# decoder.net
KiCad netlist of a schematic drawn in EAGLE
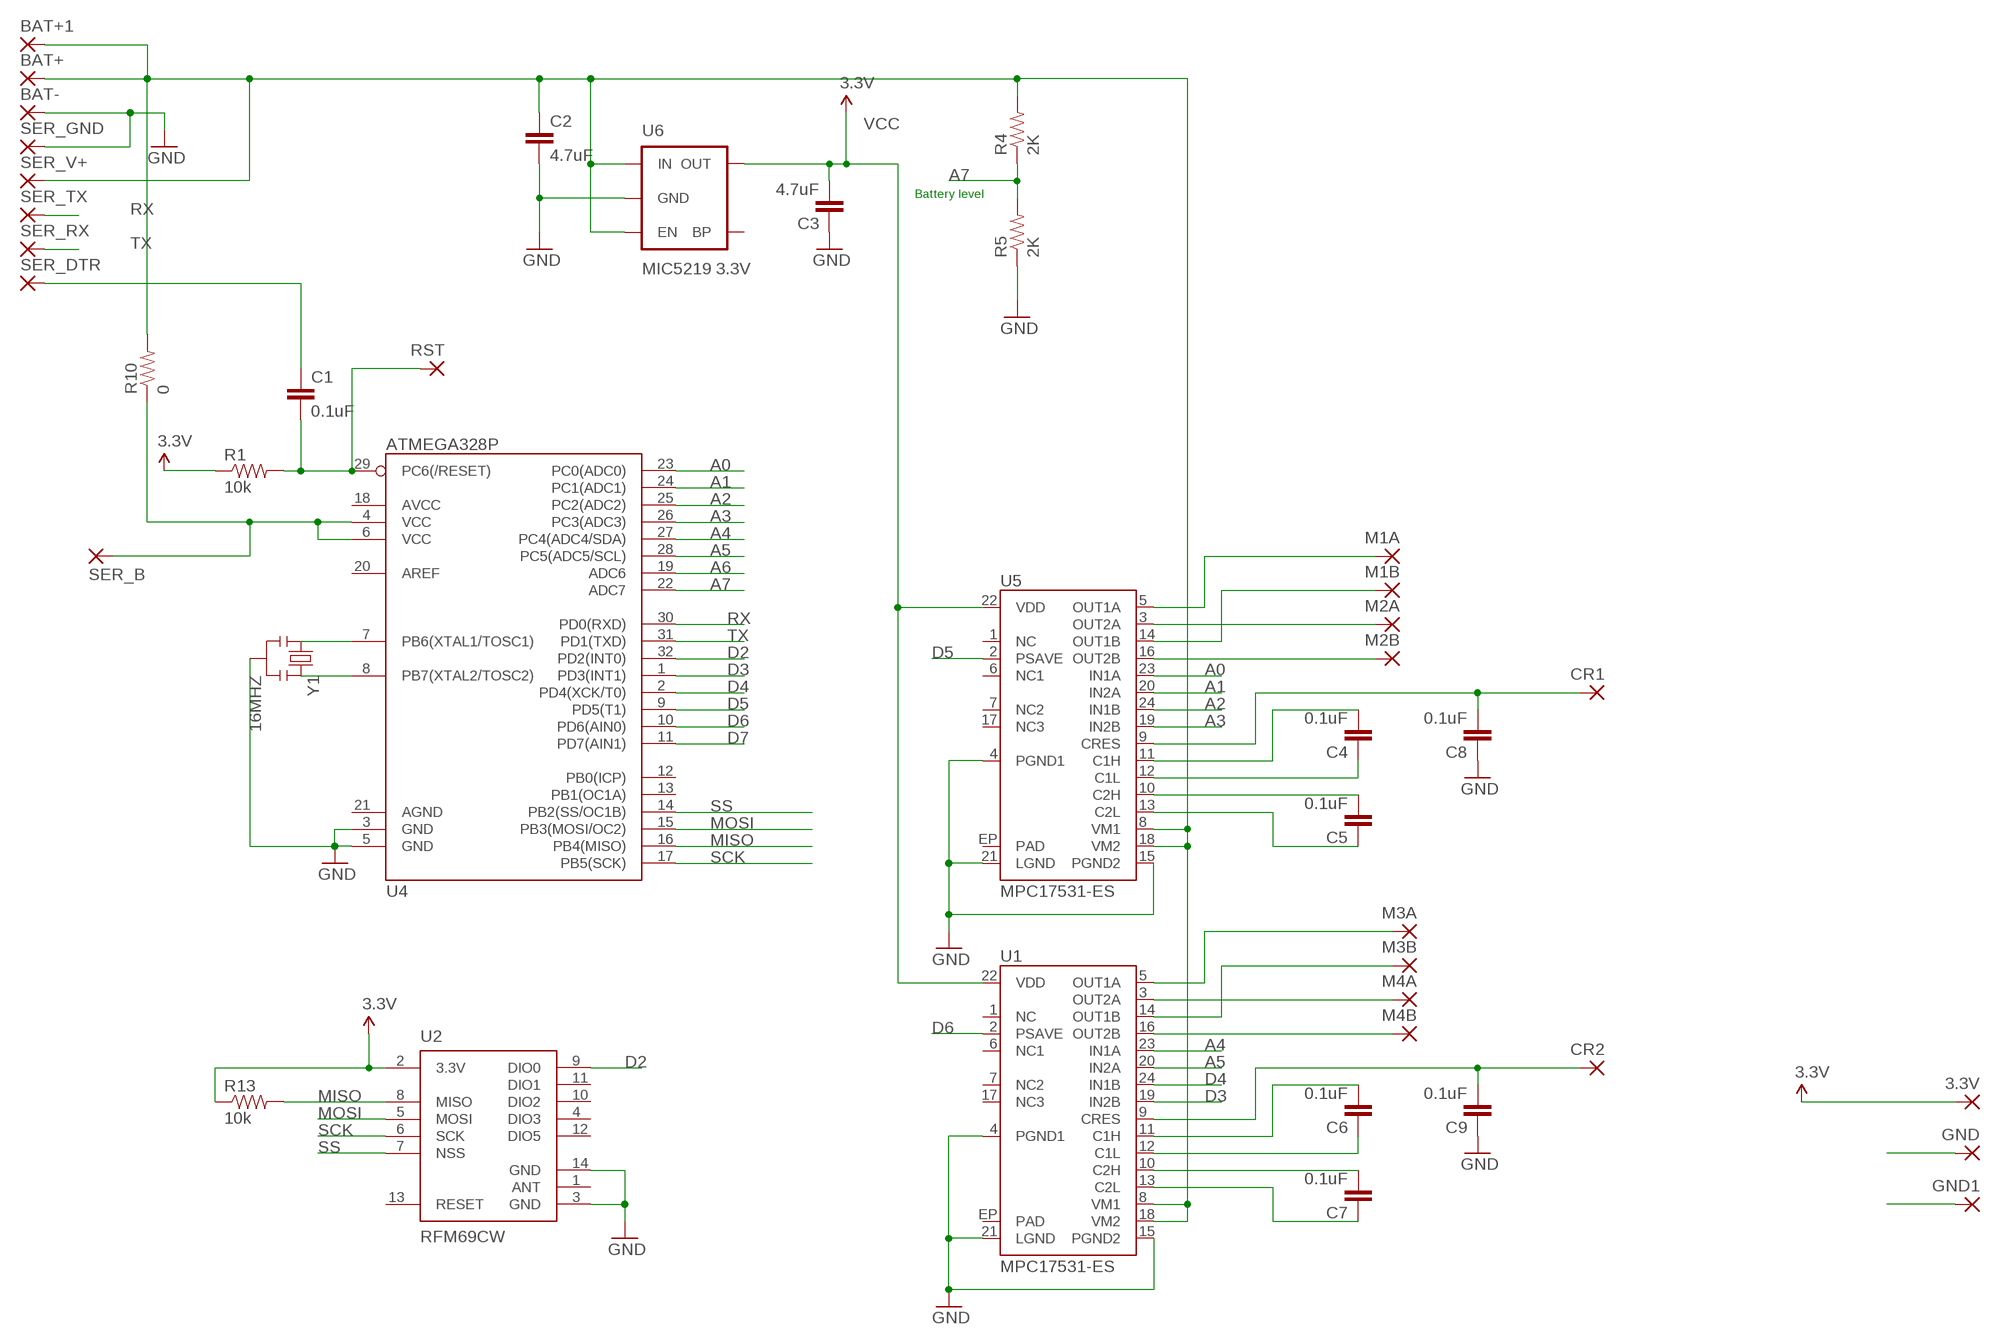
[diagram p0: schematic, sheet 1]

(export (version "E")
  (design (tool "Eeschema 10.0.6"))
  (components
    (comp (ref "3.3V")
      (value "SMD2")
      (footprint "eagle-import:SMD1,27-2,54")
      (libsource (lib "eagle-import") (part "SMD2"))
    )
    (comp (ref "BAT+")
      (value "SMD2")
      (footprint "eagle-import:SMD1,27-2,54")
      (libsource (lib "eagle-import") (part "SMD2"))
    )
    (comp (ref "BAT+1")
      (value "SMD2")
      (footprint "eagle-import:SMD1,27-2,54")
      (libsource (lib "eagle-import") (part "SMD2"))
    )
    (comp (ref "BAT-")
      (value "SMD2")
      (footprint "eagle-import:SMD1,27-2,54")
      (libsource (lib "eagle-import") (part "SMD2"))
    )
    (comp (ref "C1")
      (value "0.1uF")
      (footprint "eagle-import:0805")
      (libsource (lib "eagle-import") (part "CAP0805"))
    )
    (comp (ref "C2")
      (value "4.7uF")
      (footprint "eagle-import:0805")
      (libsource (lib "eagle-import") (part "CAP0805"))
    )
    (comp (ref "C3")
      (value "4.7uF")
      (footprint "eagle-import:0805")
      (libsource (lib "eagle-import") (part "CAP0805"))
    )
    (comp (ref "C4")
      (value "0.1uF")
      (footprint "eagle-import:0805")
      (libsource (lib "eagle-import") (part "CAP0805"))
    )
    (comp (ref "C5")
      (value "0.1uF")
      (footprint "eagle-import:0805")
      (libsource (lib "eagle-import") (part "CAP0805"))
    )
    (comp (ref "C6")
      (value "0.1uF")
      (footprint "eagle-import:0805")
      (libsource (lib "eagle-import") (part "CAP0805"))
    )
    (comp (ref "C7")
      (value "0.1uF")
      (footprint "eagle-import:0805")
      (libsource (lib "eagle-import") (part "CAP0805"))
    )
    (comp (ref "C8")
      (value "0.1uF")
      (footprint "eagle-import:0805")
      (libsource (lib "eagle-import") (part "CAP0805"))
    )
    (comp (ref "C9")
      (value "0.1uF")
      (footprint "eagle-import:0805")
      (libsource (lib "eagle-import") (part "CAP0805"))
    )
    (comp (ref "CR1")
      (value "SMD2")
      (footprint "eagle-import:SMD1,27-2,54")
      (libsource (lib "eagle-import") (part "SMD2"))
    )
    (comp (ref "CR2")
      (value "SMD2")
      (footprint "eagle-import:SMD1,27-2,54")
      (libsource (lib "eagle-import") (part "SMD2"))
    )
    (comp (ref "GND")
      (value "SMD2")
      (footprint "eagle-import:SMD1,27-2,54")
      (libsource (lib "eagle-import") (part "SMD2"))
    )
    (comp (ref "GND1")
      (value "SMD2")
      (footprint "eagle-import:SMD1,27-2,54")
      (libsource (lib "eagle-import") (part "SMD2"))
    )
    (comp (ref "M1A")
      (value "SMD2")
      (footprint "eagle-import:SMD1,27-2,54")
      (libsource (lib "eagle-import") (part "SMD2"))
    )
    (comp (ref "M1B")
      (value "SMD2")
      (footprint "eagle-import:SMD1,27-2,54")
      (libsource (lib "eagle-import") (part "SMD2"))
    )
    (comp (ref "M2A")
      (value "SMD2")
      (footprint "eagle-import:SMD1,27-2,54")
      (libsource (lib "eagle-import") (part "SMD2"))
    )
    (comp (ref "M2B")
      (value "SMD2")
      (footprint "eagle-import:SMD1,27-2,54")
      (libsource (lib "eagle-import") (part "SMD2"))
    )
    (comp (ref "M3A")
      (value "SMD2")
      (footprint "eagle-import:SMD1,27-2,54")
      (libsource (lib "eagle-import") (part "SMD2"))
    )
    (comp (ref "M3B")
      (value "SMD2")
      (footprint "eagle-import:SMD1,27-2,54")
      (libsource (lib "eagle-import") (part "SMD2"))
    )
    (comp (ref "M4A")
      (value "SMD2")
      (footprint "eagle-import:SMD1,27-2,54")
      (libsource (lib "eagle-import") (part "SMD2"))
    )
    (comp (ref "M4B")
      (value "SMD2")
      (footprint "eagle-import:SMD1,27-2,54")
      (libsource (lib "eagle-import") (part "SMD2"))
    )
    (comp (ref "R1")
      (value "10k")
      (footprint "eagle-import:0603-RES")
      (libsource (lib "eagle-import") (part "RESISTOR0603-RES"))
    )
    (comp (ref "R4")
      (value "2K")
      (footprint "eagle-import:0603-RES")
      (libsource (lib "eagle-import") (part "RESISTOR0603-RES"))
    )
    (comp (ref "R5")
      (value "2K")
      (footprint "eagle-import:0603-RES")
      (libsource (lib "eagle-import") (part "RESISTOR0603-RES"))
    )
    (comp (ref "R10")
      (value "0")
      (footprint "eagle-import:0603-RES")
      (libsource (lib "eagle-import") (part "RESISTOR0603-RES"))
    )
    (comp (ref "R13")
      (value "10k")
      (footprint "eagle-import:0603-RES")
      (libsource (lib "eagle-import") (part "RESISTOR0603-RES"))
    )
    (comp (ref "RST")
      (value "SMD2")
      (footprint "eagle-import:SMD1,27-2,54")
      (libsource (lib "eagle-import") (part "SMD2"))
    )
    (comp (ref "SER_B")
      (value "SMD2")
      (footprint "eagle-import:SMD1,27-2,54")
      (libsource (lib "eagle-import") (part "SMD2"))
    )
    (comp (ref "SER_DTR")
      (value "SMD2")
      (footprint "eagle-import:SMD1,27-2,54")
      (libsource (lib "eagle-import") (part "SMD2"))
    )
    (comp (ref "SER_GND")
      (value "SMD2")
      (footprint "eagle-import:SMD1,27-2,54")
      (libsource (lib "eagle-import") (part "SMD2"))
    )
    (comp (ref "SER_RX")
      (value "SMD2")
      (footprint "eagle-import:SMD1,27-2,54")
      (libsource (lib "eagle-import") (part "SMD2"))
    )
    (comp (ref "SER_TX")
      (value "SMD2")
      (footprint "eagle-import:SMD1,27-2,54")
      (libsource (lib "eagle-import") (part "SMD2"))
    )
    (comp (ref "SER_V+")
      (value "SMD2")
      (footprint "eagle-import:SMD1,27-2,54")
      (libsource (lib "eagle-import") (part "SMD2"))
    )
    (comp (ref "U1")
      (value "MPC17531-ES")
      (footprint "eagle-import:QFN-24_ALT2")
      (libsource (lib "eagle-import") (part "MPC17531-ES"))
    )
    (comp (ref "U2")
      (value "RFM69CW")
      (footprint "eagle-import:RFM69CW-XXXS2")
      (libsource (lib "eagle-import") (part "RFM69CW"))
    )
    (comp (ref "U4")
      (value "ATMEGA328P")
      (footprint "eagle-import:TQFP32-08")
      (libsource (lib "eagle-import") (part "ATMEGA328_SMT"))
    )
    (comp (ref "U5")
      (value "MPC17531-ES")
      (footprint "eagle-import:QFN-24_ALT2")
      (libsource (lib "eagle-import") (part "MPC17531-ES"))
    )
    (comp (ref "U6")
      (value "MIC5219 3.3V")
      (footprint "eagle-import:SOT23-5")
      (libsource (lib "eagle-import") (part "V_REG_MIC52193.3V"))
    )
    (comp (ref "Y1")
      (value "16MHZ")
      (footprint "eagle-import:RESONATOR-SMD")
      (libsource (lib "eagle-import") (part "RESONATOR16MHZ"))
    )
  )
  (nets
    (net (code "1") (name "/A0") (class "Default")
      (node (ref "U4") (pin "23") (pinfunction "PC0(ADC0)_23") (pintype "bidirectional"))
      (node (ref "U5") (pin "23") (pinfunction "IN1A_23") (pintype "bidirectional"))
    )
    (net (code "2") (name "/A1") (class "Default")
      (node (ref "U4") (pin "24") (pinfunction "PC1(ADC1)_24") (pintype "bidirectional"))
      (node (ref "U5") (pin "20") (pinfunction "IN2A_20") (pintype "bidirectional"))
    )
    (net (code "3") (name "/A2") (class "Default")
      (node (ref "U4") (pin "25") (pinfunction "PC2(ADC2)_25") (pintype "bidirectional"))
      (node (ref "U5") (pin "24") (pinfunction "IN1B_24") (pintype "bidirectional"))
    )
    (net (code "4") (name "/A3") (class "Default")
      (node (ref "U4") (pin "26") (pinfunction "PC3(ADC3)_26") (pintype "bidirectional"))
      (node (ref "U5") (pin "19") (pinfunction "IN2B_19") (pintype "bidirectional"))
    )
    (net (code "5") (name "/A4") (class "Default")
      (node (ref "U1") (pin "23") (pinfunction "IN1A_23") (pintype "bidirectional"))
      (node (ref "U4") (pin "27") (pinfunction "PC4(ADC4/SDA)_27") (pintype "bidirectional"))
    )
    (net (code "6") (name "/A5") (class "Default")
      (node (ref "U1") (pin "20") (pinfunction "IN2A_20") (pintype "bidirectional"))
      (node (ref "U4") (pin "28") (pinfunction "PC5(ADC5/SCL)_28") (pintype "bidirectional"))
    )
    (net (code "7") (name "/A6") (class "Default")
      (node (ref "U4") (pin "19") (pinfunction "ADC6_19") (pintype "bidirectional"))
    )
    (net (code "8") (name "/A7") (class "Default")
      (node (ref "R4") (pin "1") (pinfunction "1_1") (pintype "passive"))
      (node (ref "R5") (pin "2") (pinfunction "2_2") (pintype "passive"))
      (node (ref "U4") (pin "22") (pinfunction "ADC7_22") (pintype "bidirectional"))
    )
    (net (code "9") (name "/D2") (class "Default")
      (node (ref "U2") (pin "9") (pinfunction "DIO0_9") (pintype "bidirectional"))
      (node (ref "U4") (pin "32") (pinfunction "PD2(INT0)_32") (pintype "bidirectional"))
    )
    (net (code "10") (name "/D3") (class "Default")
      (node (ref "U1") (pin "19") (pinfunction "IN2B_19") (pintype "bidirectional"))
      (node (ref "U4") (pin "1") (pinfunction "PD3(INT1)_1") (pintype "bidirectional"))
    )
    (net (code "11") (name "/D4") (class "Default")
      (node (ref "U1") (pin "24") (pinfunction "IN1B_24") (pintype "bidirectional"))
      (node (ref "U4") (pin "2") (pinfunction "PD4(XCK/T0)_2") (pintype "bidirectional"))
    )
    (net (code "12") (name "/D5") (class "Default")
      (node (ref "U4") (pin "9") (pinfunction "PD5(T1)_9") (pintype "bidirectional"))
      (node (ref "U5") (pin "2") (pinfunction "PSAVE_2") (pintype "bidirectional"))
    )
    (net (code "13") (name "/D6") (class "Default")
      (node (ref "U1") (pin "2") (pinfunction "PSAVE_2") (pintype "bidirectional"))
      (node (ref "U4") (pin "10") (pinfunction "PD6(AIN0)_10") (pintype "bidirectional"))
    )
    (net (code "14") (name "/D7") (class "Default")
      (node (ref "U4") (pin "11") (pinfunction "PD7(AIN1)_11") (pintype "bidirectional"))
    )
    (net (code "15") (name "/MISO") (class "Default")
      (node (ref "R13") (pin "2") (pinfunction "2_2") (pintype "passive"))
      (node (ref "U2") (pin "8") (pinfunction "MISO_8") (pintype "bidirectional"))
      (node (ref "U4") (pin "16") (pinfunction "PB4(MISO)_16") (pintype "bidirectional"))
    )
    (net (code "16") (name "/MOSI") (class "Default")
      (node (ref "U2") (pin "5") (pinfunction "MOSI_5") (pintype "input"))
      (node (ref "U4") (pin "15") (pinfunction "PB3(MOSI/OC2)_15") (pintype "bidirectional"))
    )
    (net (code "17") (name "/RX") (class "Default")
      (node (ref "SER_TX") (pin "1") (pinfunction "P_1") (pintype "passive"))
      (node (ref "U4") (pin "30") (pinfunction "PD0(RXD)_30") (pintype "bidirectional"))
    )
    (net (code "18") (name "/SCK") (class "Default")
      (node (ref "U2") (pin "6") (pinfunction "SCK_6") (pintype "input"))
      (node (ref "U4") (pin "17") (pinfunction "PB5(SCK)_17") (pintype "bidirectional"))
    )
    (net (code "19") (name "/SS") (class "Default")
      (node (ref "U2") (pin "7") (pinfunction "NSS_7") (pintype "input"))
      (node (ref "U4") (pin "14") (pinfunction "PB2(SS/OC1B)_14") (pintype "bidirectional"))
    )
    (net (code "20") (name "/TX") (class "Default")
      (node (ref "SER_RX") (pin "1") (pinfunction "P_1") (pintype "passive"))
      (node (ref "U4") (pin "31") (pinfunction "PD1(TXD)_31") (pintype "bidirectional"))
    )
    (net (code "21") (name "3.3V") (class "Default")
      (node (ref "3.3V") (pin "1") (pinfunction "P_1") (pintype "passive"))
      (node (ref "C3") (pin "2") (pinfunction "2_2") (pintype "passive"))
      (node (ref "R1") (pin "1") (pinfunction "1_1") (pintype "passive"))
      (node (ref "R13") (pin "1") (pinfunction "1_1") (pintype "passive"))
      (node (ref "U1") (pin "22") (pinfunction "VDD_22") (pintype "bidirectional"))
      (node (ref "U2") (pin "2") (pinfunction "3.3V_2") (pintype "power_in"))
      (node (ref "U5") (pin "22") (pinfunction "VDD_22") (pintype "bidirectional"))
      (node (ref "U6") (pin "5") (pinfunction "OUT_5") (pintype "passive"))
    )
    (net (code "22") (name "GND") (class "Default")
      (node (ref "BAT-") (pin "1") (pinfunction "P_1") (pintype "passive"))
      (node (ref "C2") (pin "2") (pinfunction "2_2") (pintype "passive"))
      (node (ref "C3") (pin "1") (pinfunction "1_1") (pintype "passive"))
      (node (ref "C8") (pin "1") (pinfunction "1_1") (pintype "passive"))
      (node (ref "C9") (pin "1") (pinfunction "1_1") (pintype "passive"))
      (node (ref "GND") (pin "1") (pinfunction "P_1") (pintype "passive"))
      (node (ref "GND1") (pin "1") (pinfunction "P_1") (pintype "passive"))
      (node (ref "R5") (pin "1") (pinfunction "1_1") (pintype "passive"))
      (node (ref "SER_GND") (pin "1") (pinfunction "P_1") (pintype "passive"))
      (node (ref "U1") (pin "15") (pinfunction "PGND2_15") (pintype "bidirectional"))
      (node (ref "U1") (pin "21") (pinfunction "LGND_21") (pintype "bidirectional"))
      (node (ref "U1") (pin "4") (pinfunction "PGND1_4") (pintype "bidirectional"))
      (node (ref "U2") (pin "14") (pinfunction "GND_14") (pintype "power_in"))
      (node (ref "U2") (pin "3") (pinfunction "GND_3") (pintype "power_in"))
      (node (ref "U4") (pin "3") (pinfunction "GND_3") (pintype "bidirectional"))
      (node (ref "U4") (pin "5") (pinfunction "GND_5") (pintype "bidirectional"))
      (node (ref "U5") (pin "15") (pinfunction "PGND2_15") (pintype "bidirectional"))
      (node (ref "U5") (pin "21") (pinfunction "LGND_21") (pintype "bidirectional"))
      (node (ref "U5") (pin "4") (pinfunction "PGND1_4") (pintype "bidirectional"))
      (node (ref "U6") (pin "2") (pinfunction "GND_2") (pintype "input"))
      (node (ref "Y1") (pin "2") (pinfunction "2_2") (pintype "passive"))
    )
    (net (code "23") (name "Net-(BAT+-P)") (class "Default")
      (node (ref "BAT+") (pin "1") (pinfunction "P_1") (pintype "passive"))
      (node (ref "BAT+1") (pin "1") (pinfunction "P_1") (pintype "passive"))
      (node (ref "C2") (pin "1") (pinfunction "1_1") (pintype "passive"))
      (node (ref "R10") (pin "2") (pinfunction "2_2") (pintype "passive"))
      (node (ref "R4") (pin "2") (pinfunction "2_2") (pintype "passive"))
      (node (ref "SER_V+") (pin "1") (pinfunction "P_1") (pintype "passive"))
      (node (ref "U1") (pin "18") (pinfunction "VM2_18") (pintype "bidirectional"))
      (node (ref "U1") (pin "8") (pinfunction "VM1_8") (pintype "bidirectional"))
      (node (ref "U5") (pin "18") (pinfunction "VM2_18") (pintype "bidirectional"))
      (node (ref "U5") (pin "8") (pinfunction "VM1_8") (pintype "bidirectional"))
      (node (ref "U6") (pin "1") (pinfunction "IN_1") (pintype "input"))
      (node (ref "U6") (pin "3") (pinfunction "EN_3") (pintype "input"))
    )
    (net (code "24") (name "Net-(CR1-P)") (class "Default")
      (node (ref "C8") (pin "2") (pinfunction "2_2") (pintype "passive"))
      (node (ref "CR1") (pin "1") (pinfunction "P_1") (pintype "passive"))
      (node (ref "U5") (pin "9") (pinfunction "CRES_9") (pintype "bidirectional"))
    )
    (net (code "25") (name "Net-(CR2-P)") (class "Default")
      (node (ref "C9") (pin "2") (pinfunction "2_2") (pintype "passive"))
      (node (ref "CR2") (pin "1") (pinfunction "P_1") (pintype "passive"))
      (node (ref "U1") (pin "9") (pinfunction "CRES_9") (pintype "bidirectional"))
    )
    (net (code "26") (name "Net-(M1A-P)") (class "Default")
      (node (ref "M1A") (pin "1") (pinfunction "P_1") (pintype "passive"))
      (node (ref "U5") (pin "5") (pinfunction "OUT1A_5") (pintype "bidirectional"))
    )
    (net (code "27") (name "Net-(M1B-P)") (class "Default")
      (node (ref "M1B") (pin "1") (pinfunction "P_1") (pintype "passive"))
      (node (ref "U5") (pin "14") (pinfunction "OUT1B_14") (pintype "bidirectional"))
    )
    (net (code "28") (name "Net-(M2A-P)") (class "Default")
      (node (ref "M2A") (pin "1") (pinfunction "P_1") (pintype "passive"))
      (node (ref "U5") (pin "3") (pinfunction "OUT2A_3") (pintype "bidirectional"))
    )
    (net (code "29") (name "Net-(M2B-P)") (class "Default")
      (node (ref "M2B") (pin "1") (pinfunction "P_1") (pintype "passive"))
      (node (ref "U5") (pin "16") (pinfunction "OUT2B_16") (pintype "bidirectional"))
    )
    (net (code "30") (name "Net-(M3A-P)") (class "Default")
      (node (ref "M3A") (pin "1") (pinfunction "P_1") (pintype "passive"))
      (node (ref "U1") (pin "5") (pinfunction "OUT1A_5") (pintype "bidirectional"))
    )
    (net (code "31") (name "Net-(M3B-P)") (class "Default")
      (node (ref "M3B") (pin "1") (pinfunction "P_1") (pintype "passive"))
      (node (ref "U1") (pin "14") (pinfunction "OUT1B_14") (pintype "bidirectional"))
    )
    (net (code "32") (name "Net-(M4A-P)") (class "Default")
      (node (ref "M4A") (pin "1") (pinfunction "P_1") (pintype "passive"))
      (node (ref "U1") (pin "3") (pinfunction "OUT2A_3") (pintype "bidirectional"))
    )
    (net (code "33") (name "Net-(M4B-P)") (class "Default")
      (node (ref "M4B") (pin "1") (pinfunction "P_1") (pintype "passive"))
      (node (ref "U1") (pin "16") (pinfunction "OUT2B_16") (pintype "bidirectional"))
    )
    (net (code "34") (name "Net-(RST-P)") (class "Default")
      (node (ref "C1") (pin "2") (pinfunction "2_2") (pintype "passive"))
      (node (ref "R1") (pin "2") (pinfunction "2_2") (pintype "passive"))
      (node (ref "RST") (pin "1") (pinfunction "P_1") (pintype "passive"))
      (node (ref "U4") (pin "29") (pinfunction "PC6(/RESET)_29") (pintype "bidirectional"))
    )
    (net (code "35") (name "Net-(SER_B-P)") (class "Default")
      (node (ref "R10") (pin "1") (pinfunction "1_1") (pintype "passive"))
      (node (ref "SER_B") (pin "1") (pinfunction "P_1") (pintype "passive"))
      (node (ref "U4") (pin "4") (pinfunction "VCC_4") (pintype "bidirectional"))
      (node (ref "U4") (pin "6") (pinfunction "VCC_6") (pintype "bidirectional"))
    )
    (net (code "36") (name "Net-(SER_DTR-P)") (class "Default")
      (node (ref "C1") (pin "1") (pinfunction "1_1") (pintype "passive"))
      (node (ref "SER_DTR") (pin "1") (pinfunction "P_1") (pintype "passive"))
    )
    (net (code "37") (name "Net-(U1-C1H)") (class "Default")
      (node (ref "C6") (pin "2") (pinfunction "2_2") (pintype "passive"))
      (node (ref "U1") (pin "11") (pinfunction "C1H_11") (pintype "bidirectional"))
    )
    (net (code "38") (name "Net-(U1-C1L)") (class "Default")
      (node (ref "C6") (pin "1") (pinfunction "1_1") (pintype "passive"))
      (node (ref "U1") (pin "12") (pinfunction "C1L_12") (pintype "bidirectional"))
    )
    (net (code "39") (name "Net-(U1-C2H)") (class "Default")
      (node (ref "C7") (pin "2") (pinfunction "2_2") (pintype "passive"))
      (node (ref "U1") (pin "10") (pinfunction "C2H_10") (pintype "bidirectional"))
    )
    (net (code "40") (name "Net-(U1-C2L)") (class "Default")
      (node (ref "C7") (pin "1") (pinfunction "1_1") (pintype "passive"))
      (node (ref "U1") (pin "13") (pinfunction "C2L_13") (pintype "bidirectional"))
    )
    (net (code "41") (name "Net-(U4-PB6(XTAL1{slash}TOSC1))") (class "Default")
      (node (ref "U4") (pin "7") (pinfunction "PB6(XTAL1/TOSC1)_7") (pintype "bidirectional"))
      (node (ref "Y1") (pin "1") (pinfunction "1_1") (pintype "passive"))
    )
    (net (code "42") (name "Net-(U4-PB7(XTAL2{slash}TOSC2))") (class "Default")
      (node (ref "U4") (pin "8") (pinfunction "PB7(XTAL2/TOSC2)_8") (pintype "bidirectional"))
      (node (ref "Y1") (pin "3") (pinfunction "3_3") (pintype "passive"))
    )
    (net (code "43") (name "Net-(U5-C1H)") (class "Default")
      (node (ref "C4") (pin "2") (pinfunction "2_2") (pintype "passive"))
      (node (ref "U5") (pin "11") (pinfunction "C1H_11") (pintype "bidirectional"))
    )
    (net (code "44") (name "Net-(U5-C1L)") (class "Default")
      (node (ref "C4") (pin "1") (pinfunction "1_1") (pintype "passive"))
      (node (ref "U5") (pin "12") (pinfunction "C1L_12") (pintype "bidirectional"))
    )
    (net (code "45") (name "Net-(U5-C2H)") (class "Default")
      (node (ref "C5") (pin "2") (pinfunction "2_2") (pintype "passive"))
      (node (ref "U5") (pin "10") (pinfunction "C2H_10") (pintype "bidirectional"))
    )
    (net (code "46") (name "Net-(U5-C2L)") (class "Default")
      (node (ref "C5") (pin "1") (pinfunction "1_1") (pintype "passive"))
      (node (ref "U5") (pin "13") (pinfunction "C2L_13") (pintype "bidirectional"))
    )
    (net (code "47") (name "unconnected-(U1-NC-Pad1)") (class "Default")
      (node (ref "U1") (pin "1") (pinfunction "NC_1") (pintype "bidirectional"))
    )
    (net (code "48") (name "unconnected-(U1-NC1-Pad6)") (class "Default")
      (node (ref "U1") (pin "6") (pinfunction "NC1_6") (pintype "bidirectional"))
    )
    (net (code "49") (name "unconnected-(U1-NC2-Pad7)") (class "Default")
      (node (ref "U1") (pin "7") (pinfunction "NC2_7") (pintype "bidirectional"))
    )
    (net (code "50") (name "unconnected-(U1-NC3-Pad17)") (class "Default")
      (node (ref "U1") (pin "17") (pinfunction "NC3_17") (pintype "bidirectional"))
    )
    (net (code "51") (name "unconnected-(U1-PAD-PadEP)") (class "Default")
      (node (ref "U1") (pin "EP") (pinfunction "PAD_EP") (pintype "bidirectional"))
    )
    (net (code "52") (name "unconnected-(U2-ANT-Pad1)") (class "Default")
      (node (ref "U2") (pin "1") (pinfunction "ANT_1") (pintype "passive"))
    )
    (net (code "53") (name "unconnected-(U2-DIO1-Pad11)") (class "Default")
      (node (ref "U2") (pin "11") (pinfunction "DIO1_11") (pintype "bidirectional"))
    )
    (net (code "54") (name "unconnected-(U2-DIO2-Pad10)") (class "Default")
      (node (ref "U2") (pin "10") (pinfunction "DIO2_10") (pintype "bidirectional"))
    )
    (net (code "55") (name "unconnected-(U2-DIO3-Pad4)") (class "Default")
      (node (ref "U2") (pin "4") (pinfunction "DIO3_4") (pintype "bidirectional"))
    )
    (net (code "56") (name "unconnected-(U2-DIO5-Pad12)") (class "Default")
      (node (ref "U2") (pin "12") (pinfunction "DIO5_12") (pintype "bidirectional"))
    )
    (net (code "57") (name "unconnected-(U2-RESET-Pad13)") (class "Default")
      (node (ref "U2") (pin "13") (pinfunction "RESET_13") (pintype "input"))
    )
    (net (code "58") (name "unconnected-(U4-AGND-Pad21)") (class "Default")
      (node (ref "U4") (pin "21") (pinfunction "AGND_21") (pintype "bidirectional"))
    )
    (net (code "59") (name "unconnected-(U4-AREF-Pad20)") (class "Default")
      (node (ref "U4") (pin "20") (pinfunction "AREF_20") (pintype "bidirectional"))
    )
    (net (code "60") (name "unconnected-(U4-AVCC-Pad18)") (class "Default")
      (node (ref "U4") (pin "18") (pinfunction "AVCC_18") (pintype "bidirectional"))
    )
    (net (code "61") (name "unconnected-(U4-PB0(ICP)-Pad12)") (class "Default")
      (node (ref "U4") (pin "12") (pinfunction "PB0(ICP)_12") (pintype "bidirectional"))
    )
    (net (code "62") (name "unconnected-(U4-PB1(OC1A)-Pad13)") (class "Default")
      (node (ref "U4") (pin "13") (pinfunction "PB1(OC1A)_13") (pintype "bidirectional"))
    )
    (net (code "63") (name "unconnected-(U5-NC-Pad1)") (class "Default")
      (node (ref "U5") (pin "1") (pinfunction "NC_1") (pintype "bidirectional"))
    )
    (net (code "64") (name "unconnected-(U5-NC1-Pad6)") (class "Default")
      (node (ref "U5") (pin "6") (pinfunction "NC1_6") (pintype "bidirectional"))
    )
    (net (code "65") (name "unconnected-(U5-NC2-Pad7)") (class "Default")
      (node (ref "U5") (pin "7") (pinfunction "NC2_7") (pintype "bidirectional"))
    )
    (net (code "66") (name "unconnected-(U5-NC3-Pad17)") (class "Default")
      (node (ref "U5") (pin "17") (pinfunction "NC3_17") (pintype "bidirectional"))
    )
    (net (code "67") (name "unconnected-(U5-PAD-PadEP)") (class "Default")
      (node (ref "U5") (pin "EP") (pinfunction "PAD_EP") (pintype "bidirectional"))
    )
    (net (code "68") (name "unconnected-(U6-BP-Pad4)") (class "Default")
      (node (ref "U6") (pin "4") (pinfunction "BP_4") (pintype "input"))
    )
  )
)
